# Sheet_1_2021-05-29.net
KiCad netlist of a schematic drawn in Altium Designer
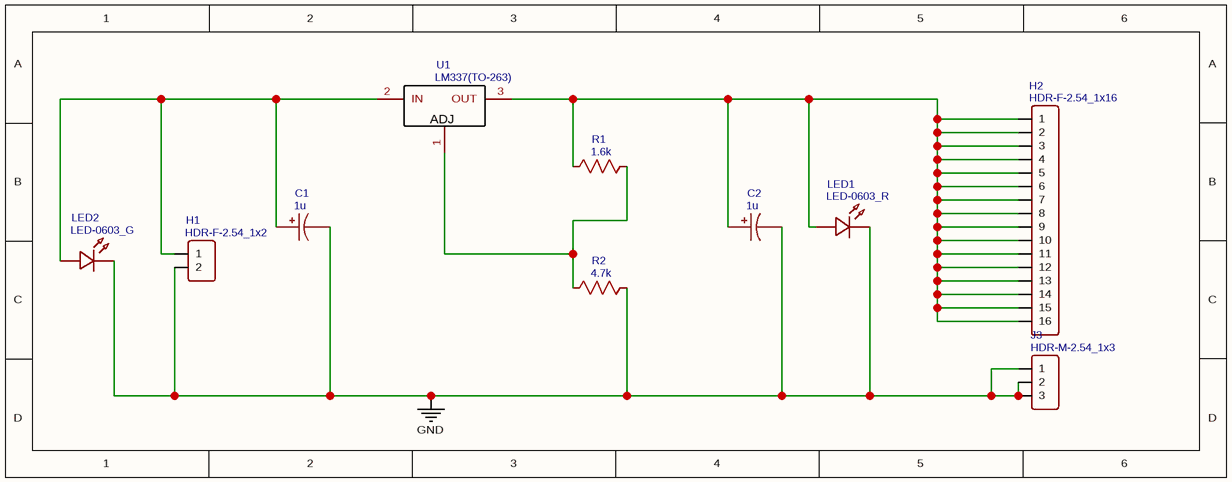
[diagram p0: Sheet_1_2021-05-29.schdoc]

(export (version "E")
  (design (tool "Eeschema 10.0.6"))
  (components
    (comp (ref "C1")
      (value "1u")
      (fields (field (name "CONTRIBUTOR") "LCEDA_Lib"))
      (libsource (lib "altium-import") (part "root_0_1u_"))
    )
    (comp (ref "C2")
      (value "1u")
      (fields (field (name "CONTRIBUTOR") "LCEDA_Lib"))
      (libsource (lib "altium-import") (part "root_0_1u_"))
    )
    (comp (ref "H1")
      (value "HDR-F-2.54_1x2")
      (fields (field (name "BOM_SUPPLIER PART") "C49661") (field (name "CONTRIBUTOR") "LCEDA_Lib"))
      (libsource (lib "altium-import") (part "root_0_HDR-F-2.54_1x2_"))
    )
    (comp (ref "H2")
      (value "HDR-F-2.54_1x16")
      (fields (field (name "BOM_SUPPLIER PART") "C66987") (field (name "CONTRIBUTOR") "LCEDA_Lib"))
      (libsource (lib "altium-import") (part "root_0_HDR-F-2.54_1x16_"))
    )
    (comp (ref "J3")
      (value "HDR-M-2.54_1x3")
      (fields (field (name "BOM_SUPPLIER PART") "C180248") (field (name "CONTRIBUTOR") "LCEDA_Lib"))
      (libsource (lib "altium-import") (part "root_0_HDR-M-2.54_1x3_"))
    )
    (comp (ref "LED1")
      (value "LED-0603_R")
      (fields
        (field (name "BOM_MANUFACTURER PART") "19-217/R6C-AL1M2VY/3T")
        (field (name "BOM_SUPPLIER PART") "C72044")
        (field (name "CONTRIBUTOR") "LCEDA_01")
      )
      (libsource (lib "altium-import") (part "root_0_LED-0603_R_"))
    )
    (comp (ref "LED2")
      (value "LED-0603_G")
      (fields
        (field (name "BOM_MANUFACTURER PART") "19-217/GHC-YR1S2/3T")
        (field (name "BOM_SUPPLIER PART") "C72043")
        (field (name "CONTRIBUTOR") "LCEDA_Lib")
      )
      (libsource (lib "altium-import") (part "root_0_LED-0603_G_"))
    )
    (comp (ref "R1")
      (value "1.6k")
      (fields (field (name "CONTRIBUTOR") "LCEDA_Lib"))
      (libsource (lib "altium-import") (part "root_0_1.6k_"))
    )
    (comp (ref "R2")
      (value "4.7k")
      (fields (field (name "CONTRIBUTOR") "LCEDA_Lib"))
      (libsource (lib "altium-import") (part "root_0_4.7k_"))
    )
    (comp (ref "U1")
      (value "LM337(TO-263)")
      (fields
        (field (name "BOM_MANUFACTURER PART") "LM337D2TG")
        (field (name "BOM_SUPPLIER PART") "C146782")
        (field (name "CONTRIBUTOR") "LCEDA_Lib")
      )
      (libsource (lib "altium-import") (part "root_0_LM337(TO-263)_"))
    )
  )
  (nets
    (net (code "1") (name "GND") (class "Default")
      (node (ref "C1") (pin "2") (pinfunction "2_2") (pintype "passive"))
      (node (ref "C2") (pin "2") (pinfunction "2_2") (pintype "passive"))
      (node (ref "H1") (pin "2") (pinfunction "2_2") (pintype "passive"))
      (node (ref "J3") (pin "1") (pinfunction "1_1") (pintype "passive"))
      (node (ref "J3") (pin "2") (pinfunction "2_2") (pintype "passive"))
      (node (ref "J3") (pin "3") (pinfunction "3_3") (pintype "passive"))
      (node (ref "LED1") (pin "2") (pinfunction "2_2") (pintype "passive"))
      (node (ref "LED2") (pin "2") (pinfunction "2_2") (pintype "passive"))
      (node (ref "R2") (pin "2") (pinfunction "2_2") (pintype "passive"))
    )
    (net (code "2") (name "Net-(U1-ADJ)") (class "Default")
      (node (ref "R1") (pin "2") (pinfunction "2_2") (pintype "passive"))
      (node (ref "R2") (pin "1") (pinfunction "1_1") (pintype "passive"))
      (node (ref "U1") (pin "1") (pinfunction "ADJ_1") (pintype "passive"))
    )
    (net (code "3") (name "Net-(U1-IN)") (class "Default")
      (node (ref "C1") (pin "1") (pinfunction "1_1") (pintype "passive"))
      (node (ref "H1") (pin "1") (pinfunction "1_1") (pintype "passive"))
      (node (ref "LED2") (pin "1") (pinfunction "1_1") (pintype "passive"))
      (node (ref "U1") (pin "2") (pinfunction "IN_2") (pintype "passive"))
    )
    (net (code "4") (name "Net-(U1-OUT)") (class "Default")
      (node (ref "C2") (pin "1") (pinfunction "1_1") (pintype "passive"))
      (node (ref "H2") (pin "1") (pinfunction "1_1") (pintype "passive"))
      (node (ref "H2") (pin "10") (pinfunction "10_10") (pintype "passive"))
      (node (ref "H2") (pin "11") (pinfunction "11_11") (pintype "passive"))
      (node (ref "H2") (pin "12") (pinfunction "12_12") (pintype "passive"))
      (node (ref "H2") (pin "13") (pinfunction "13_13") (pintype "passive"))
      (node (ref "H2") (pin "14") (pinfunction "14_14") (pintype "passive"))
      (node (ref "H2") (pin "15") (pinfunction "15_15") (pintype "passive"))
      (node (ref "H2") (pin "16") (pinfunction "16_16") (pintype "passive"))
      (node (ref "H2") (pin "2") (pinfunction "2_2") (pintype "passive"))
      (node (ref "H2") (pin "3") (pinfunction "3_3") (pintype "passive"))
      (node (ref "H2") (pin "4") (pinfunction "4_4") (pintype "passive"))
      (node (ref "H2") (pin "5") (pinfunction "5_5") (pintype "passive"))
      (node (ref "H2") (pin "6") (pinfunction "6_6") (pintype "passive"))
      (node (ref "H2") (pin "7") (pinfunction "7_7") (pintype "passive"))
      (node (ref "H2") (pin "8") (pinfunction "8_8") (pintype "passive"))
      (node (ref "H2") (pin "9") (pinfunction "9_9") (pintype "passive"))
      (node (ref "LED1") (pin "1") (pinfunction "1_1") (pintype "passive"))
      (node (ref "R1") (pin "1") (pinfunction "1_1") (pintype "passive"))
      (node (ref "U1") (pin "3") (pinfunction "OUT_3") (pintype "passive"))
    )
  )
)
